# 1_power.net
KiCad netlist of a schematic drawn in Altium Designer
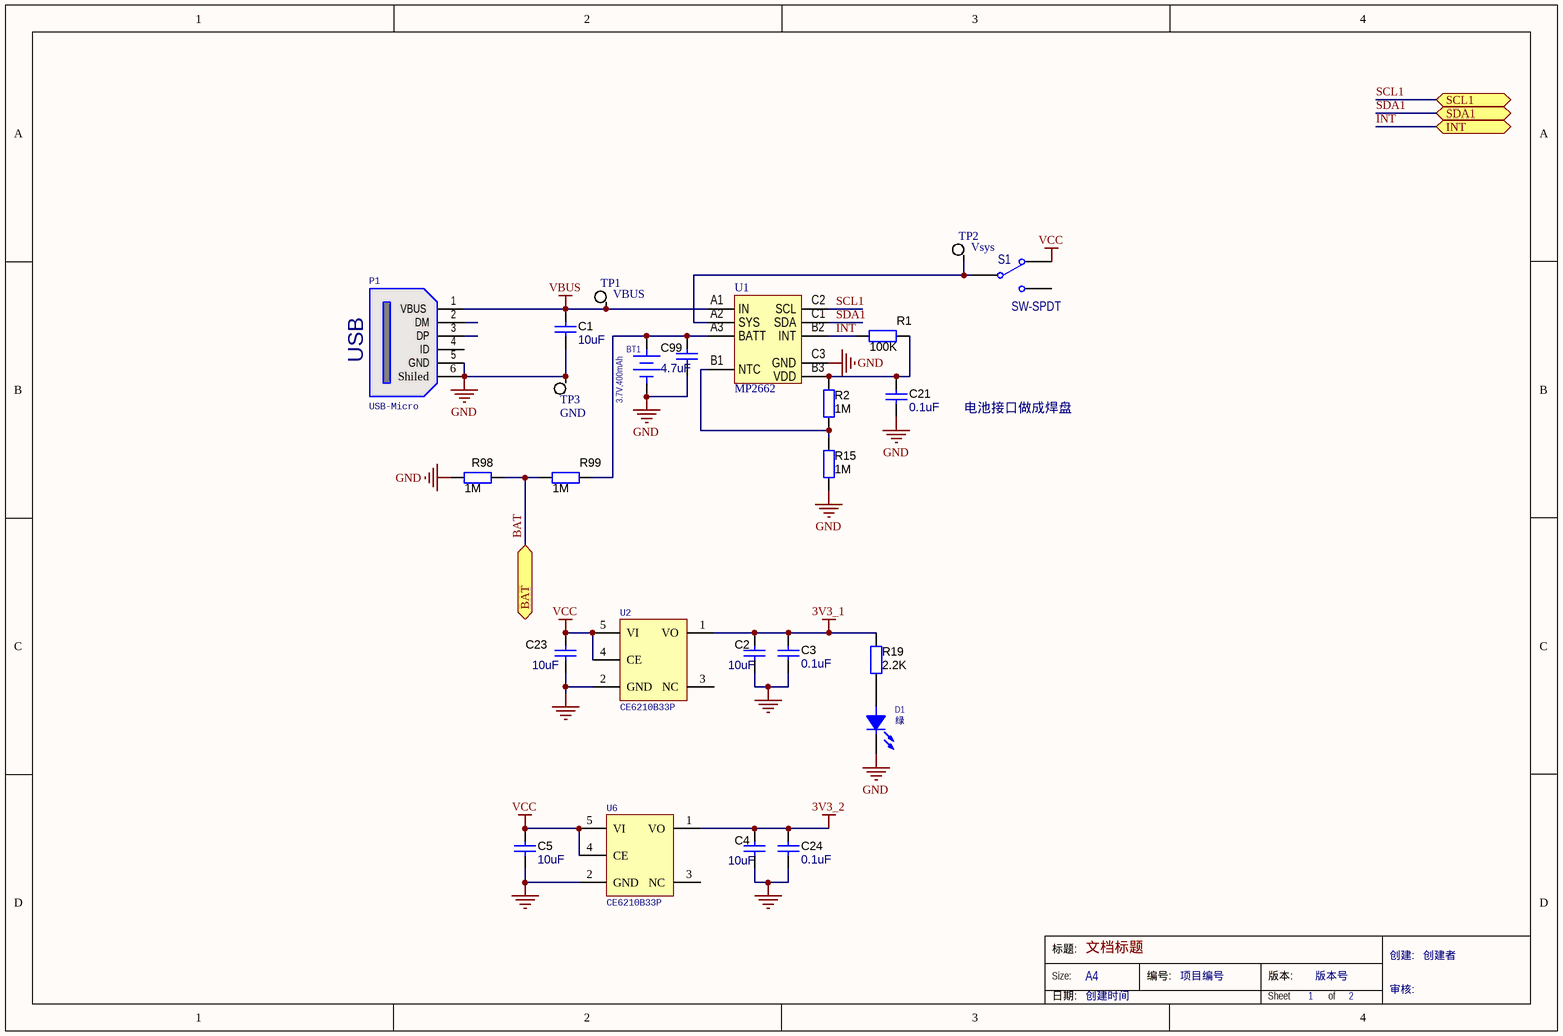
[diagram p0: 1.power.SchDoc]

(export (version "E")
  (design (tool "Eeschema 10.0.6"))
  (components
    (comp (ref "BT1")
      (value "3.7V,400mAh")
      (footprint "焊盘")
      (description "4.2V Li-lon")
      (fields (field (name "MANUFACTURER") "?"))
      (libsource (lib "03.常用器件") (part "Battery"))
    )
    (comp (ref "C1")
      (value "10uF")
      (footprint "0603")
      (description "CAP, CERM, 0.01uF, 100V, +/-5%, X7R, 0603")
      (fields (field (name "PARTNUMBER") "06031C103JAT2A") (field (name "MANUFACTURER") "AVX"))
      (libsource (lib "03.常用器件") (part "CAP1_npol"))
    )
    (comp (ref "C2")
      (value "10uF")
      (footprint "0603")
      (description "CAP, CERM, 0.01uF, 100V, +/-5%, X7R, 0603")
      (fields (field (name "PARTNUMBER") "06031C103JAT2A") (field (name "MANUFACTURER") "AVX"))
      (libsource (lib "03.常用器件") (part "CAP1_npol"))
    )
    (comp (ref "C3")
      (value "0.1uF")
      (footprint "0402")
      (description "CAP, CERM, 0.01uF, 100V, +/-5%, X7R, 0603")
      (fields (field (name "PARTNUMBER") "06031C103JAT2A") (field (name "MANUFACTURER") "AVX"))
      (libsource (lib "03.常用器件") (part "CAP1_npol"))
    )
    (comp (ref "C4")
      (value "10uF")
      (footprint "0603")
      (description "CAP, CERM, 0.01uF, 100V, +/-5%, X7R, 0603")
      (fields (field (name "PARTNUMBER") "06031C103JAT2A") (field (name "MANUFACTURER") "AVX"))
      (libsource (lib "03.常用器件") (part "CAP1_npol"))
    )
    (comp (ref "C5")
      (value "10uF")
      (footprint "0603")
      (description "CAP, CERM, 0.01uF, 100V, +/-5%, X7R, 0603")
      (fields (field (name "PARTNUMBER") "06031C103JAT2A") (field (name "MANUFACTURER") "AVX"))
      (libsource (lib "03.常用器件") (part "CAP1_npol"))
    )
    (comp (ref "C21")
      (value "0.1uF")
      (footprint "0603")
      (description "CAP, CERM, 0.01uF, 100V, +/-5%, X7R, 0603")
      (fields (field (name "PARTNUMBER") "06031C103JAT2A") (field (name "MANUFACTURER") "AVX"))
      (libsource (lib "03.常用器件") (part "CAP1_npol"))
    )
    (comp (ref "C23")
      (value "10uF")
      (footprint "0603")
      (description "CAP, CERM, 0.01uF, 100V, +/-5%, X7R, 0603")
      (fields (field (name "PARTNUMBER") "06031C103JAT2A") (field (name "MANUFACTURER") "AVX"))
      (libsource (lib "03.常用器件") (part "CAP1_npol"))
    )
    (comp (ref "C24")
      (value "0.1uF")
      (footprint "0402")
      (description "CAP, CERM, 0.01uF, 100V, +/-5%, X7R, 0603")
      (fields (field (name "PARTNUMBER") "06031C103JAT2A") (field (name "MANUFACTURER") "AVX"))
      (libsource (lib "03.常用器件") (part "CAP1_npol"))
    )
    (comp (ref "C99")
      (value "4.7uF")
      (footprint "0603")
      (description "CAP, CERM, 0.01uF, 100V, +/-5%, X7R, 0603")
      (fields (field (name "PARTNUMBER") "06031C103JAT2A") (field (name "MANUFACTURER") "AVX"))
      (libsource (lib "03.常用器件") (part "CAP1_npol"))
    )
    (comp (ref "D1")
      (value "绿")
      (footprint "0603LED")
      (fields (field (name "MANUFACTURER") "?"))
      (libsource (lib "03.常用器件") (part "LED1"))
    )
    (comp (ref "P1")
      (value "USB-Micro")
      (footprint "MICRO_USB2")
      (description "USB Connector")
      (libsource (lib "misc") (part "USB-Micro"))
    )
    (comp (ref "R1")
      (value "100K")
      (footprint "0402")
      (description "RES, 1.0k ohm, 5%, 0.1W, 0603")
      (fields
        (field (name "PARTNUMBER") "RC0603JR-071KL")
        (field (name "MANUFACTURER") "Yageo America")
        (field (name "PUBLISHER") "Texas Instruments")
      )
      (libsource (lib "03.常用器件") (part "RES1"))
    )
    (comp (ref "R2")
      (value "1M")
      (footprint "0402")
      (description "RES, 1.0k ohm, 5%, 0.1W, 0603")
      (fields
        (field (name "PARTNUMBER") "RC0603JR-071KL")
        (field (name "MANUFACTURER") "Yageo America")
        (field (name "PUBLISHER") "Texas Instruments")
      )
      (libsource (lib "") (part "RES1_1"))
    )
    (comp (ref "R15")
      (value "1M")
      (footprint "0402")
      (description "RES, 1.0k ohm, 5%, 0.1W, 0603")
      (fields
        (field (name "PARTNUMBER") "RC0603JR-071KL")
        (field (name "MANUFACTURER") "Yageo America")
        (field (name "PUBLISHER") "Texas Instruments")
      )
      (libsource (lib "") (part "RES1_1"))
    )
    (comp (ref "R19")
      (value "2.2K")
      (footprint "0402")
      (description "RES, 1.0k ohm, 5%, 0.1W, 0603")
      (fields
        (field (name "PARTNUMBER") "RC0603JR-071KL")
        (field (name "MANUFACTURER") "Yageo America")
        (field (name "PUBLISHER") "Texas Instruments")
      )
      (libsource (lib "") (part "RES1_1"))
    )
    (comp (ref "R98")
      (value "1M")
      (footprint "0402")
      (description "RES, 1.0k ohm, 5%, 0.1W, 0603")
      (fields
        (field (name "PARTNUMBER") "RC0603JR-071KL")
        (field (name "MANUFACTURER") "Yageo America")
        (field (name "PUBLISHER") "Texas Instruments")
      )
      (libsource (lib "03.常用器件") (part "RES1"))
    )
    (comp (ref "R99")
      (value "1M")
      (footprint "0402")
      (description "RES, 1.0k ohm, 5%, 0.1W, 0603")
      (fields
        (field (name "PARTNUMBER") "RC0603JR-071KL")
        (field (name "MANUFACTURER") "Yageo America")
        (field (name "PUBLISHER") "Texas Instruments")
      )
      (libsource (lib "03.常用器件") (part "RES1"))
    )
    (comp (ref "S1")
      (value "SW-SPDT")
      (footprint "SW2")
      (description "SPDT Subminiature Toggle Switch, Right Angle Mounting, Vertical Actuation")
      (fields (field (name "PUBLISHER") "Altium Limited"))
      (libsource (lib "Miscellaneous Devices") (part "SW-SPDT"))
    )
    (comp (ref "TP1")
      (value "VBUS")
      (footprint "测试点")
      (description "Test Point")
      (libsource (lib "my_Schlib") (part "TP"))
    )
    (comp (ref "TP2")
      (value "Vsys")
      (footprint "测试点")
      (description "Test Point")
      (libsource (lib "my_Schlib") (part "TP"))
    )
    (comp (ref "TP3")
      (value "GND")
      (footprint "测试点")
      (description "Test Point")
      (libsource (lib "my_Schlib") (part "TP"))
    )
    (comp (ref "U1") (value "MP2662") (footprint "WLCSP-9") (libsource (lib "Schlib1") (part "MP2662")))
    (comp (ref "U2")
      (value "CE6210B33P")
      (footprint "SOT89-5")
      (libsource (lib "altium-import") (part "root_0_AP2112K_"))
    )
    (comp (ref "U6")
      (value "CE6210B33P")
      (footprint "SOT89-5")
      (libsource (lib "altium-import") (part "root_0_AP2112K_"))
    )
  )
  (nets
    (net (code "1") (name "/BAT") (class "Default")
      (node (ref "R98") (pin "2") (pinfunction "2_2") (pintype "passive"))
      (node (ref "R99") (pin "1") (pinfunction "1_1") (pintype "passive"))
    )
    (net (code "2") (name "/INT") (class "Default")
      (node (ref "R1") (pin "1") (pinfunction "1_1") (pintype "passive"))
      (node (ref "U1") (pin "B2") (pinfunction "INT_B2") (pintype "passive"))
    )
    (net (code "3") (name "/SCL1") (class "Default")
      (node (ref "U1") (pin "C2") (pinfunction "SCL_C2") (pintype "passive"))
    )
    (net (code "4") (name "/SDA1") (class "Default")
      (node (ref "U1") (pin "C1") (pinfunction "SDA_C1") (pintype "passive"))
    )
    (net (code "5") (name "3V3_1") (class "Default")
      (node (ref "C2") (pin "1") (pinfunction "1_1") (pintype "passive"))
      (node (ref "C3") (pin "2") (pinfunction "2_2") (pintype "passive"))
      (node (ref "R19") (pin "1") (pinfunction "1_1") (pintype "passive"))
      (node (ref "U2") (pin "1") (pinfunction "VO_1") (pintype "passive"))
    )
    (net (code "6") (name "3V3_2") (class "Default")
      (node (ref "C24") (pin "2") (pinfunction "2_2") (pintype "passive"))
      (node (ref "C4") (pin "1") (pinfunction "1_1") (pintype "passive"))
      (node (ref "U6") (pin "1") (pinfunction "VO_1") (pintype "passive"))
    )
    (net (code "7") (name "GND") (class "Default")
      (node (ref "BT1") (pin "2") (pinfunction "-_2") (pintype "passive"))
      (node (ref "C1") (pin "2") (pinfunction "2_2") (pintype "passive"))
      (node (ref "C2") (pin "2") (pinfunction "2_2") (pintype "passive"))
      (node (ref "C21") (pin "2") (pinfunction "2_2") (pintype "passive"))
      (node (ref "C23") (pin "2") (pinfunction "2_2") (pintype "passive"))
      (node (ref "C24") (pin "1") (pinfunction "1_1") (pintype "passive"))
      (node (ref "C3") (pin "1") (pinfunction "1_1") (pintype "passive"))
      (node (ref "C4") (pin "2") (pinfunction "2_2") (pintype "passive"))
      (node (ref "C5") (pin "2") (pinfunction "2_2") (pintype "passive"))
      (node (ref "C99") (pin "2") (pinfunction "2_2") (pintype "passive"))
      (node (ref "D1") (pin "C") (pinfunction "CATHODE_C") (pintype "passive"))
      (node (ref "P1") (pin "5") (pinfunction "GND_5") (pintype "passive"))
      (node (ref "P1") (pin "6") (pinfunction "Shiled_6") (pintype "passive"))
      (node (ref "R15") (pin "2") (pinfunction "2_2") (pintype "passive"))
      (node (ref "R98") (pin "1") (pinfunction "1_1") (pintype "passive"))
      (node (ref "TP3") (pin "1") (pinfunction "1_1") (pintype "passive"))
      (node (ref "U1") (pin "C3") (pinfunction "GND_C3") (pintype "passive"))
      (node (ref "U2") (pin "2") (pinfunction "GND_2") (pintype "passive"))
      (node (ref "U6") (pin "2") (pinfunction "GND_2") (pintype "passive"))
    )
    (net (code "8") (name "Net-(BT1-+)") (class "Default")
      (node (ref "BT1") (pin "1") (pinfunction "+_1") (pintype "passive"))
      (node (ref "C99") (pin "1") (pinfunction "1_1") (pintype "passive"))
      (node (ref "R99") (pin "2") (pinfunction "2_2") (pintype "passive"))
      (node (ref "U1") (pin "A3") (pinfunction "BATT_A3") (pintype "passive"))
    )
    (net (code "9") (name "Net-(D1-ANODE)") (class "Default")
      (node (ref "D1") (pin "A") (pinfunction "ANODE_A") (pintype "passive"))
      (node (ref "R19") (pin "2") (pinfunction "2_2") (pintype "passive"))
    )
    (net (code "10") (name "Net-(U1-NTC)") (class "Default")
      (node (ref "R15") (pin "1") (pinfunction "1_1") (pintype "passive"))
      (node (ref "R2") (pin "2") (pinfunction "2_2") (pintype "passive"))
      (node (ref "U1") (pin "B1") (pinfunction "NTC_B1") (pintype "power_in"))
    )
    (net (code "11") (name "Net-(U1-SYS)") (class "Default")
      (node (ref "S1") (pin "2") (pinfunction "2_2") (pintype "passive"))
      (node (ref "TP2") (pin "1") (pinfunction "1_1") (pintype "passive"))
      (node (ref "U1") (pin "A2") (pinfunction "SYS_A2") (pintype "passive"))
    )
    (net (code "12") (name "Net-(U1-VDD)") (class "Default")
      (node (ref "C21") (pin "1") (pinfunction "1_1") (pintype "passive"))
      (node (ref "R1") (pin "2") (pinfunction "2_2") (pintype "passive"))
      (node (ref "R2") (pin "1") (pinfunction "1_1") (pintype "passive"))
      (node (ref "U1") (pin "B3") (pinfunction "VDD_B3") (pintype "passive"))
    )
    (net (code "13") (name "VBUS") (class "Default")
      (node (ref "C1") (pin "1") (pinfunction "1_1") (pintype "passive"))
      (node (ref "P1") (pin "1") (pinfunction "VBUS_1") (pintype "passive"))
      (node (ref "TP1") (pin "1") (pinfunction "1_1") (pintype "passive"))
      (node (ref "U1") (pin "A1") (pinfunction "IN_A1") (pintype "passive"))
    )
    (net (code "14") (name "VCC") (class "Default")
      (node (ref "C23") (pin "1") (pinfunction "1_1") (pintype "passive"))
      (node (ref "C5") (pin "1") (pinfunction "1_1") (pintype "passive"))
      (node (ref "S1") (pin "3") (pinfunction "3_3") (pintype "passive"))
      (node (ref "U2") (pin "4") (pinfunction "CE_4") (pintype "passive"))
      (node (ref "U2") (pin "5") (pinfunction "VI_5") (pintype "passive"))
      (node (ref "U6") (pin "4") (pinfunction "CE_4") (pintype "passive"))
      (node (ref "U6") (pin "5") (pinfunction "VI_5") (pintype "passive"))
    )
    (net (code "15") (name "unconnected-(P1-DM-Pad2)") (class "Default")
      (node (ref "P1") (pin "2") (pinfunction "DM_2") (pintype "passive"))
    )
    (net (code "16") (name "unconnected-(P1-DP-Pad3)") (class "Default")
      (node (ref "P1") (pin "3") (pinfunction "DP_3") (pintype "passive"))
    )
    (net (code "17") (name "unconnected-(P1-ID-Pad4)") (class "Default")
      (node (ref "P1") (pin "4") (pinfunction "ID_4") (pintype "passive"))
    )
    (net (code "18") (name "unconnected-(S1-Pad1)") (class "Default")
      (node (ref "S1") (pin "1") (pinfunction "1_1") (pintype "passive"))
    )
    (net (code "19") (name "unconnected-(U2-NC-Pad3)") (class "Default")
      (node (ref "U2") (pin "3") (pinfunction "NC_3") (pintype "passive"))
    )
    (net (code "20") (name "unconnected-(U6-NC-Pad3)") (class "Default")
      (node (ref "U6") (pin "3") (pinfunction "NC_3") (pintype "passive"))
    )
  )
)
